# protector_new.net
KiCad netlist of a schematic drawn in EAGLE
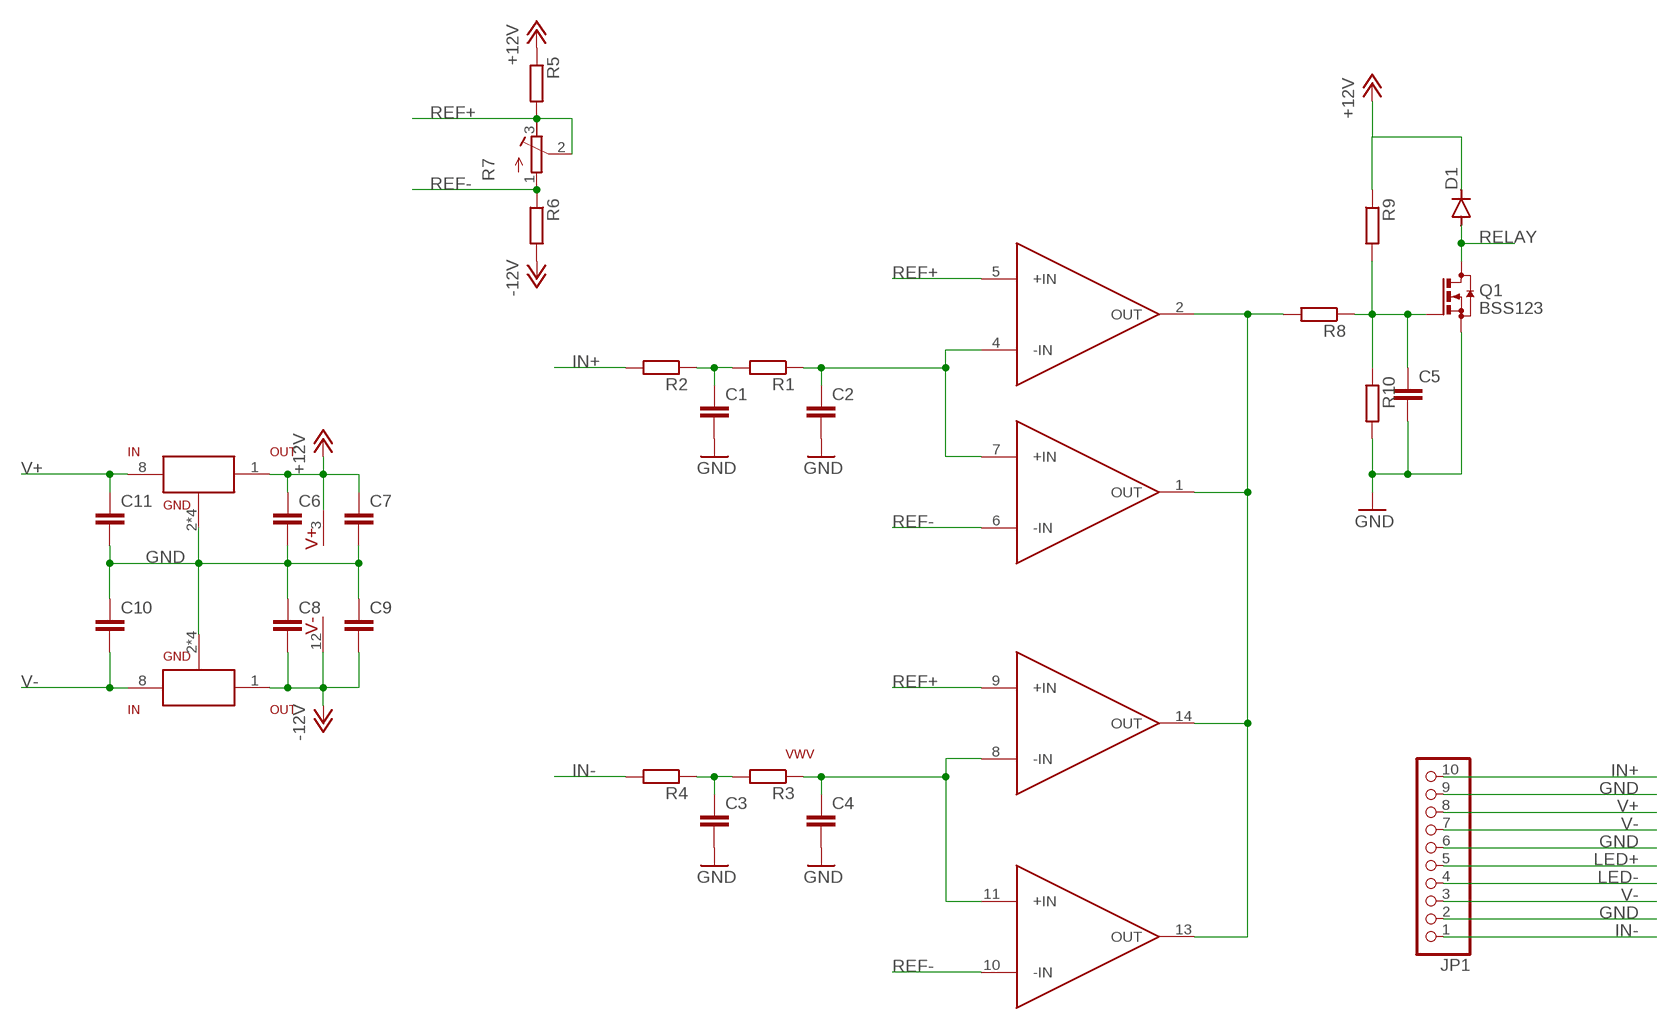
[diagram p0: schematic, sheet 1]

(export (version "E")
  (design (tool "Eeschema 10.0.6"))
  (components
    (comp (ref "C1")
      (value "C-EUC0805")
      (footprint "eagle-import:C0805")
      (libsource (lib "eagle-import") (part "C-EUC0805"))
    )
    (comp (ref "C2")
      (value "C-EUC0805")
      (footprint "eagle-import:C0805")
      (libsource (lib "eagle-import") (part "C-EUC0805"))
    )
    (comp (ref "C3")
      (value "C-EUC0805")
      (footprint "eagle-import:C0805")
      (libsource (lib "eagle-import") (part "C-EUC0805"))
    )
    (comp (ref "C4")
      (value "C-EUC0805")
      (footprint "eagle-import:C0805")
      (libsource (lib "eagle-import") (part "C-EUC0805"))
    )
    (comp (ref "C5")
      (value "C-EUC1210")
      (footprint "eagle-import:C1210")
      (libsource (lib "eagle-import") (part "C-EUC1210"))
    )
    (comp (ref "C6")
      (value "C-EUC0805")
      (footprint "eagle-import:C0805")
      (libsource (lib "eagle-import") (part "C-EUC0805"))
    )
    (comp (ref "C7")
      (value "C-EUC0805")
      (footprint "eagle-import:C0805")
      (libsource (lib "eagle-import") (part "C-EUC0805"))
    )
    (comp (ref "C8")
      (value "C-EUC0805")
      (footprint "eagle-import:C0805")
      (libsource (lib "eagle-import") (part "C-EUC0805"))
    )
    (comp (ref "C9")
      (value "C-EUC0805")
      (footprint "eagle-import:C0805")
      (libsource (lib "eagle-import") (part "C-EUC0805"))
    )
    (comp (ref "C10")
      (value "C-EUC0805")
      (footprint "eagle-import:C0805")
      (libsource (lib "eagle-import") (part "C-EUC0805"))
    )
    (comp (ref "C11")
      (value "C-EUC0805")
      (footprint "eagle-import:C0805")
      (libsource (lib "eagle-import") (part "C-EUC0805"))
    )
    (comp (ref "D1")
      (value "DIODE-SOD80C")
      (footprint "eagle-import:SOD80C")
      (libsource (lib "eagle-import") (part "DIODE-SOD80C"))
    )
    (comp (ref "JP1")
      (value "PINHD-1X10/90")
      (footprint "eagle-import:1X10_90")
      (libsource (lib "eagle-import") (part "PINHD-1X10/90"))
    )
    (comp (ref "Q1")
      (value "BSS123")
      (footprint "eagle-import:SOT23")
      (libsource (lib "eagle-import") (part "BSS123"))
    )
    (comp (ref "R1")
      (value "R-EU_MELF0204W")
      (footprint "eagle-import:MINI_MELF-0204W")
      (libsource (lib "eagle-import") (part "R-EU_MELF0204W"))
    )
    (comp (ref "R2")
      (value "R-EU_MELF0204W")
      (footprint "eagle-import:MINI_MELF-0204W")
      (libsource (lib "eagle-import") (part "R-EU_MELF0204W"))
    )
    (comp (ref "R3")
      (value "R-EU_MELF0204W")
      (footprint "eagle-import:MINI_MELF-0204W")
      (libsource (lib "eagle-import") (part "R-EU_MELF0204W"))
    )
    (comp (ref "R4")
      (value "R-EU_MELF0204W")
      (footprint "eagle-import:MINI_MELF-0204W")
      (libsource (lib "eagle-import") (part "R-EU_MELF0204W"))
    )
    (comp (ref "R5")
      (value "R-EU_MELF0204W")
      (footprint "eagle-import:MINI_MELF-0204W")
      (libsource (lib "eagle-import") (part "R-EU_MELF0204W"))
    )
    (comp (ref "R6")
      (value "R-EU_MELF0204W")
      (footprint "eagle-import:MINI_MELF-0204W")
      (libsource (lib "eagle-import") (part "R-EU_MELF0204W"))
    )
    (comp (ref "R7")
      (value "R-TRIMM3296W")
      (footprint "eagle-import:RTRIM3296W")
      (libsource (lib "eagle-import") (part "R-TRIMM3296W"))
    )
    (comp (ref "R8")
      (value "R-EU_MELF0204W")
      (footprint "eagle-import:MINI_MELF-0204W")
      (libsource (lib "eagle-import") (part "R-EU_MELF0204W"))
    )
    (comp (ref "R9")
      (value "R-EU_MELF0204W")
      (footprint "eagle-import:MINI_MELF-0204W")
      (libsource (lib "eagle-import") (part "R-EU_MELF0204W"))
    )
    (comp (ref "R10")
      (value "R-EU_MELF0204W")
      (footprint "eagle-import:MINI_MELF-0204W")
      (libsource (lib "eagle-import") (part "R-EU_MELF0204W"))
    )
    (comp (ref "U$1")
      (value "VWV")
      (footprint "eagle-import:VWV")
      (libsource (lib "eagle-import") (part "VWV"))
    )
    (comp (ref "U$2")
      (value "TLV1704TSSOP14")
      (footprint "eagle-import:TSSOP14")
      (libsource (lib "eagle-import") (part "TLV1704TSSOP14"))
    )
    (comp (ref "U$3")
      (value "MC78XXSOIC-8")
      (footprint "eagle-import:SO8")
      (libsource (lib "eagle-import") (part "MC78XXSOIC-8"))
    )
    (comp (ref "U$4")
      (value "MC79XXSOIC-8")
      (footprint "eagle-import:SO8")
      (libsource (lib "eagle-import") (part "MC79XXSOIC-8"))
    )
  )
  (nets
    (net (code "1") (name "+12V") (class "Default")
      (node (ref "C6") (pin "1") (pinfunction "1_1") (pintype "passive"))
      (node (ref "C7") (pin "1") (pinfunction "1_1") (pintype "passive"))
      (node (ref "D1") (pin "C") (pinfunction "C_C") (pintype "passive"))
      (node (ref "R5") (pin "1") (pinfunction "1_1") (pintype "passive"))
      (node (ref "R9") (pin "1") (pinfunction "1_1") (pintype "passive"))
      (node (ref "U$2") (pin "3") (pinfunction "V+_3") (pintype "bidirectional"))
      (node (ref "U$3") (pin "1") (pinfunction "OUT_1") (pintype "bidirectional"))
    )
    (net (code "2") (name "-12V") (class "Default")
      (node (ref "C8") (pin "2") (pinfunction "2_2") (pintype "passive"))
      (node (ref "C9") (pin "2") (pinfunction "2_2") (pintype "passive"))
      (node (ref "R6") (pin "2") (pinfunction "2_2") (pintype "passive"))
      (node (ref "U$2") (pin "12") (pinfunction "V-_12") (pintype "bidirectional"))
      (node (ref "U$4") (pin "1") (pinfunction "OUT_1") (pintype "bidirectional"))
    )
    (net (code "3") (name "/IN+") (class "Default")
      (node (ref "JP1") (pin "10") (pinfunction "10_10") (pintype "passive"))
      (node (ref "R2") (pin "2") (pinfunction "2_2") (pintype "passive"))
    )
    (net (code "4") (name "/IN-") (class "Default")
      (node (ref "JP1") (pin "1") (pinfunction "1_1") (pintype "passive"))
      (node (ref "R4") (pin "2") (pinfunction "2_2") (pintype "passive"))
    )
    (net (code "5") (name "/LED+") (class "Default")
      (node (ref "JP1") (pin "5") (pinfunction "5_5") (pintype "passive"))
    )
    (net (code "6") (name "/LED-") (class "Default")
      (node (ref "JP1") (pin "4") (pinfunction "4_4") (pintype "passive"))
    )
    (net (code "7") (name "/REF+") (class "Default")
      (node (ref "R5") (pin "2") (pinfunction "2_2") (pintype "passive"))
      (node (ref "R7") (pin "2") (pinfunction "S_2") (pintype "passive"))
      (node (ref "R7") (pin "3") (pinfunction "E_3") (pintype "passive"))
      (node (ref "U$2") (pin "5") (pinfunction "+IN_5") (pintype "bidirectional"))
      (node (ref "U$2") (pin "9") (pinfunction "+IN_9") (pintype "bidirectional"))
    )
    (net (code "8") (name "/REF-") (class "Default")
      (node (ref "R6") (pin "1") (pinfunction "1_1") (pintype "passive"))
      (node (ref "R7") (pin "1") (pinfunction "A_1") (pintype "passive"))
      (node (ref "U$2") (pin "10") (pinfunction "-IN_10") (pintype "bidirectional"))
      (node (ref "U$2") (pin "6") (pinfunction "-IN_6") (pintype "bidirectional"))
    )
    (net (code "9") (name "/RELAY") (class "Default")
      (node (ref "D1") (pin "A") (pinfunction "A_A") (pintype "passive"))
      (node (ref "Q1") (pin "3") (pinfunction "D_3") (pintype "passive"))
    )
    (net (code "10") (name "/V+") (class "Default")
      (node (ref "C11") (pin "1") (pinfunction "1_1") (pintype "passive"))
      (node (ref "JP1") (pin "8") (pinfunction "8_8") (pintype "passive"))
      (node (ref "U$3") (pin "8") (pinfunction "IN_8") (pintype "bidirectional"))
    )
    (net (code "11") (name "/V-") (class "Default")
      (node (ref "C10") (pin "2") (pinfunction "2_2") (pintype "passive"))
      (node (ref "JP1") (pin "3") (pinfunction "3_3") (pintype "passive"))
      (node (ref "JP1") (pin "7") (pinfunction "7_7") (pintype "passive"))
      (node (ref "U$4") (pin "8") (pinfunction "IN_8") (pintype "bidirectional"))
    )
    (net (code "12") (name "GND") (class "Default")
      (node (ref "C1") (pin "2") (pinfunction "2_2") (pintype "passive"))
      (node (ref "C10") (pin "1") (pinfunction "1_1") (pintype "passive"))
      (node (ref "C11") (pin "2") (pinfunction "2_2") (pintype "passive"))
      (node (ref "C2") (pin "2") (pinfunction "2_2") (pintype "passive"))
      (node (ref "C3") (pin "2") (pinfunction "2_2") (pintype "passive"))
      (node (ref "C4") (pin "2") (pinfunction "2_2") (pintype "passive"))
      (node (ref "C5") (pin "2") (pinfunction "2_2") (pintype "passive"))
      (node (ref "C6") (pin "2") (pinfunction "2_2") (pintype "passive"))
      (node (ref "C7") (pin "2") (pinfunction "2_2") (pintype "passive"))
      (node (ref "C8") (pin "1") (pinfunction "1_1") (pintype "passive"))
      (node (ref "C9") (pin "1") (pinfunction "1_1") (pintype "passive"))
      (node (ref "JP1") (pin "2") (pinfunction "2_2") (pintype "passive"))
      (node (ref "JP1") (pin "6") (pinfunction "6_6") (pintype "passive"))
      (node (ref "JP1") (pin "9") (pinfunction "9_9") (pintype "passive"))
      (node (ref "Q1") (pin "2") (pinfunction "S_2") (pintype "passive"))
      (node (ref "R10") (pin "2") (pinfunction "2_2") (pintype "passive"))
      (node (ref "U$3") (pin "2") (pinfunction "GND_2") (pintype "bidirectional"))
      (node (ref "U$3") (pin "3") (pinfunction "GND_3") (pintype "bidirectional"))
      (node (ref "U$3") (pin "6") (pinfunction "GND_6") (pintype "bidirectional"))
      (node (ref "U$3") (pin "7") (pinfunction "GND_7") (pintype "bidirectional"))
      (node (ref "U$4") (pin "2") (pinfunction "GND_2") (pintype "bidirectional"))
      (node (ref "U$4") (pin "3") (pinfunction "GND_3") (pintype "bidirectional"))
      (node (ref "U$4") (pin "6") (pinfunction "GND_6") (pintype "bidirectional"))
      (node (ref "U$4") (pin "7") (pinfunction "GND_7") (pintype "bidirectional"))
    )
    (net (code "13") (name "Net-(C1-Pad1)") (class "Default")
      (node (ref "C1") (pin "1") (pinfunction "1_1") (pintype "passive"))
      (node (ref "R1") (pin "2") (pinfunction "2_2") (pintype "passive"))
      (node (ref "R2") (pin "1") (pinfunction "1_1") (pintype "passive"))
    )
    (net (code "14") (name "Net-(C3-Pad1)") (class "Default")
      (node (ref "C3") (pin "1") (pinfunction "1_1") (pintype "passive"))
      (node (ref "R3") (pin "2") (pinfunction "2_2") (pintype "passive"))
      (node (ref "R4") (pin "1") (pinfunction "1_1") (pintype "passive"))
    )
    (net (code "15") (name "Net-(Q1-G)") (class "Default")
      (node (ref "C5") (pin "1") (pinfunction "1_1") (pintype "passive"))
      (node (ref "Q1") (pin "1") (pinfunction "G_1") (pintype "passive"))
      (node (ref "R10") (pin "1") (pinfunction "1_1") (pintype "passive"))
      (node (ref "R8") (pin "1") (pinfunction "1_1") (pintype "passive"))
      (node (ref "R9") (pin "2") (pinfunction "2_2") (pintype "passive"))
    )
    (net (code "16") (name "Net-(U$2A--IN)") (class "Default")
      (node (ref "C2") (pin "1") (pinfunction "1_1") (pintype "passive"))
      (node (ref "R1") (pin "1") (pinfunction "1_1") (pintype "passive"))
      (node (ref "U$2") (pin "4") (pinfunction "-IN_4") (pintype "bidirectional"))
      (node (ref "U$2") (pin "7") (pinfunction "+IN_7") (pintype "bidirectional"))
    )
    (net (code "17") (name "Net-(U$2A-OUT)") (class "Default")
      (node (ref "R8") (pin "2") (pinfunction "2_2") (pintype "passive"))
      (node (ref "U$2") (pin "1") (pinfunction "OUT_1") (pintype "bidirectional"))
      (node (ref "U$2") (pin "13") (pinfunction "OUT_13") (pintype "bidirectional"))
      (node (ref "U$2") (pin "14") (pinfunction "OUT_14") (pintype "bidirectional"))
      (node (ref "U$2") (pin "2") (pinfunction "OUT_2") (pintype "bidirectional"))
    )
    (net (code "18") (name "Net-(U$2C--IN)") (class "Default")
      (node (ref "C4") (pin "1") (pinfunction "1_1") (pintype "passive"))
      (node (ref "R3") (pin "1") (pinfunction "1_1") (pintype "passive"))
      (node (ref "U$2") (pin "11") (pinfunction "+IN_11") (pintype "bidirectional"))
      (node (ref "U$2") (pin "8") (pinfunction "-IN_8") (pintype "bidirectional"))
    )
  )
)
